# TMS570LS0914_all.net
KiCad netlist of a schematic drawn in Altium Designer
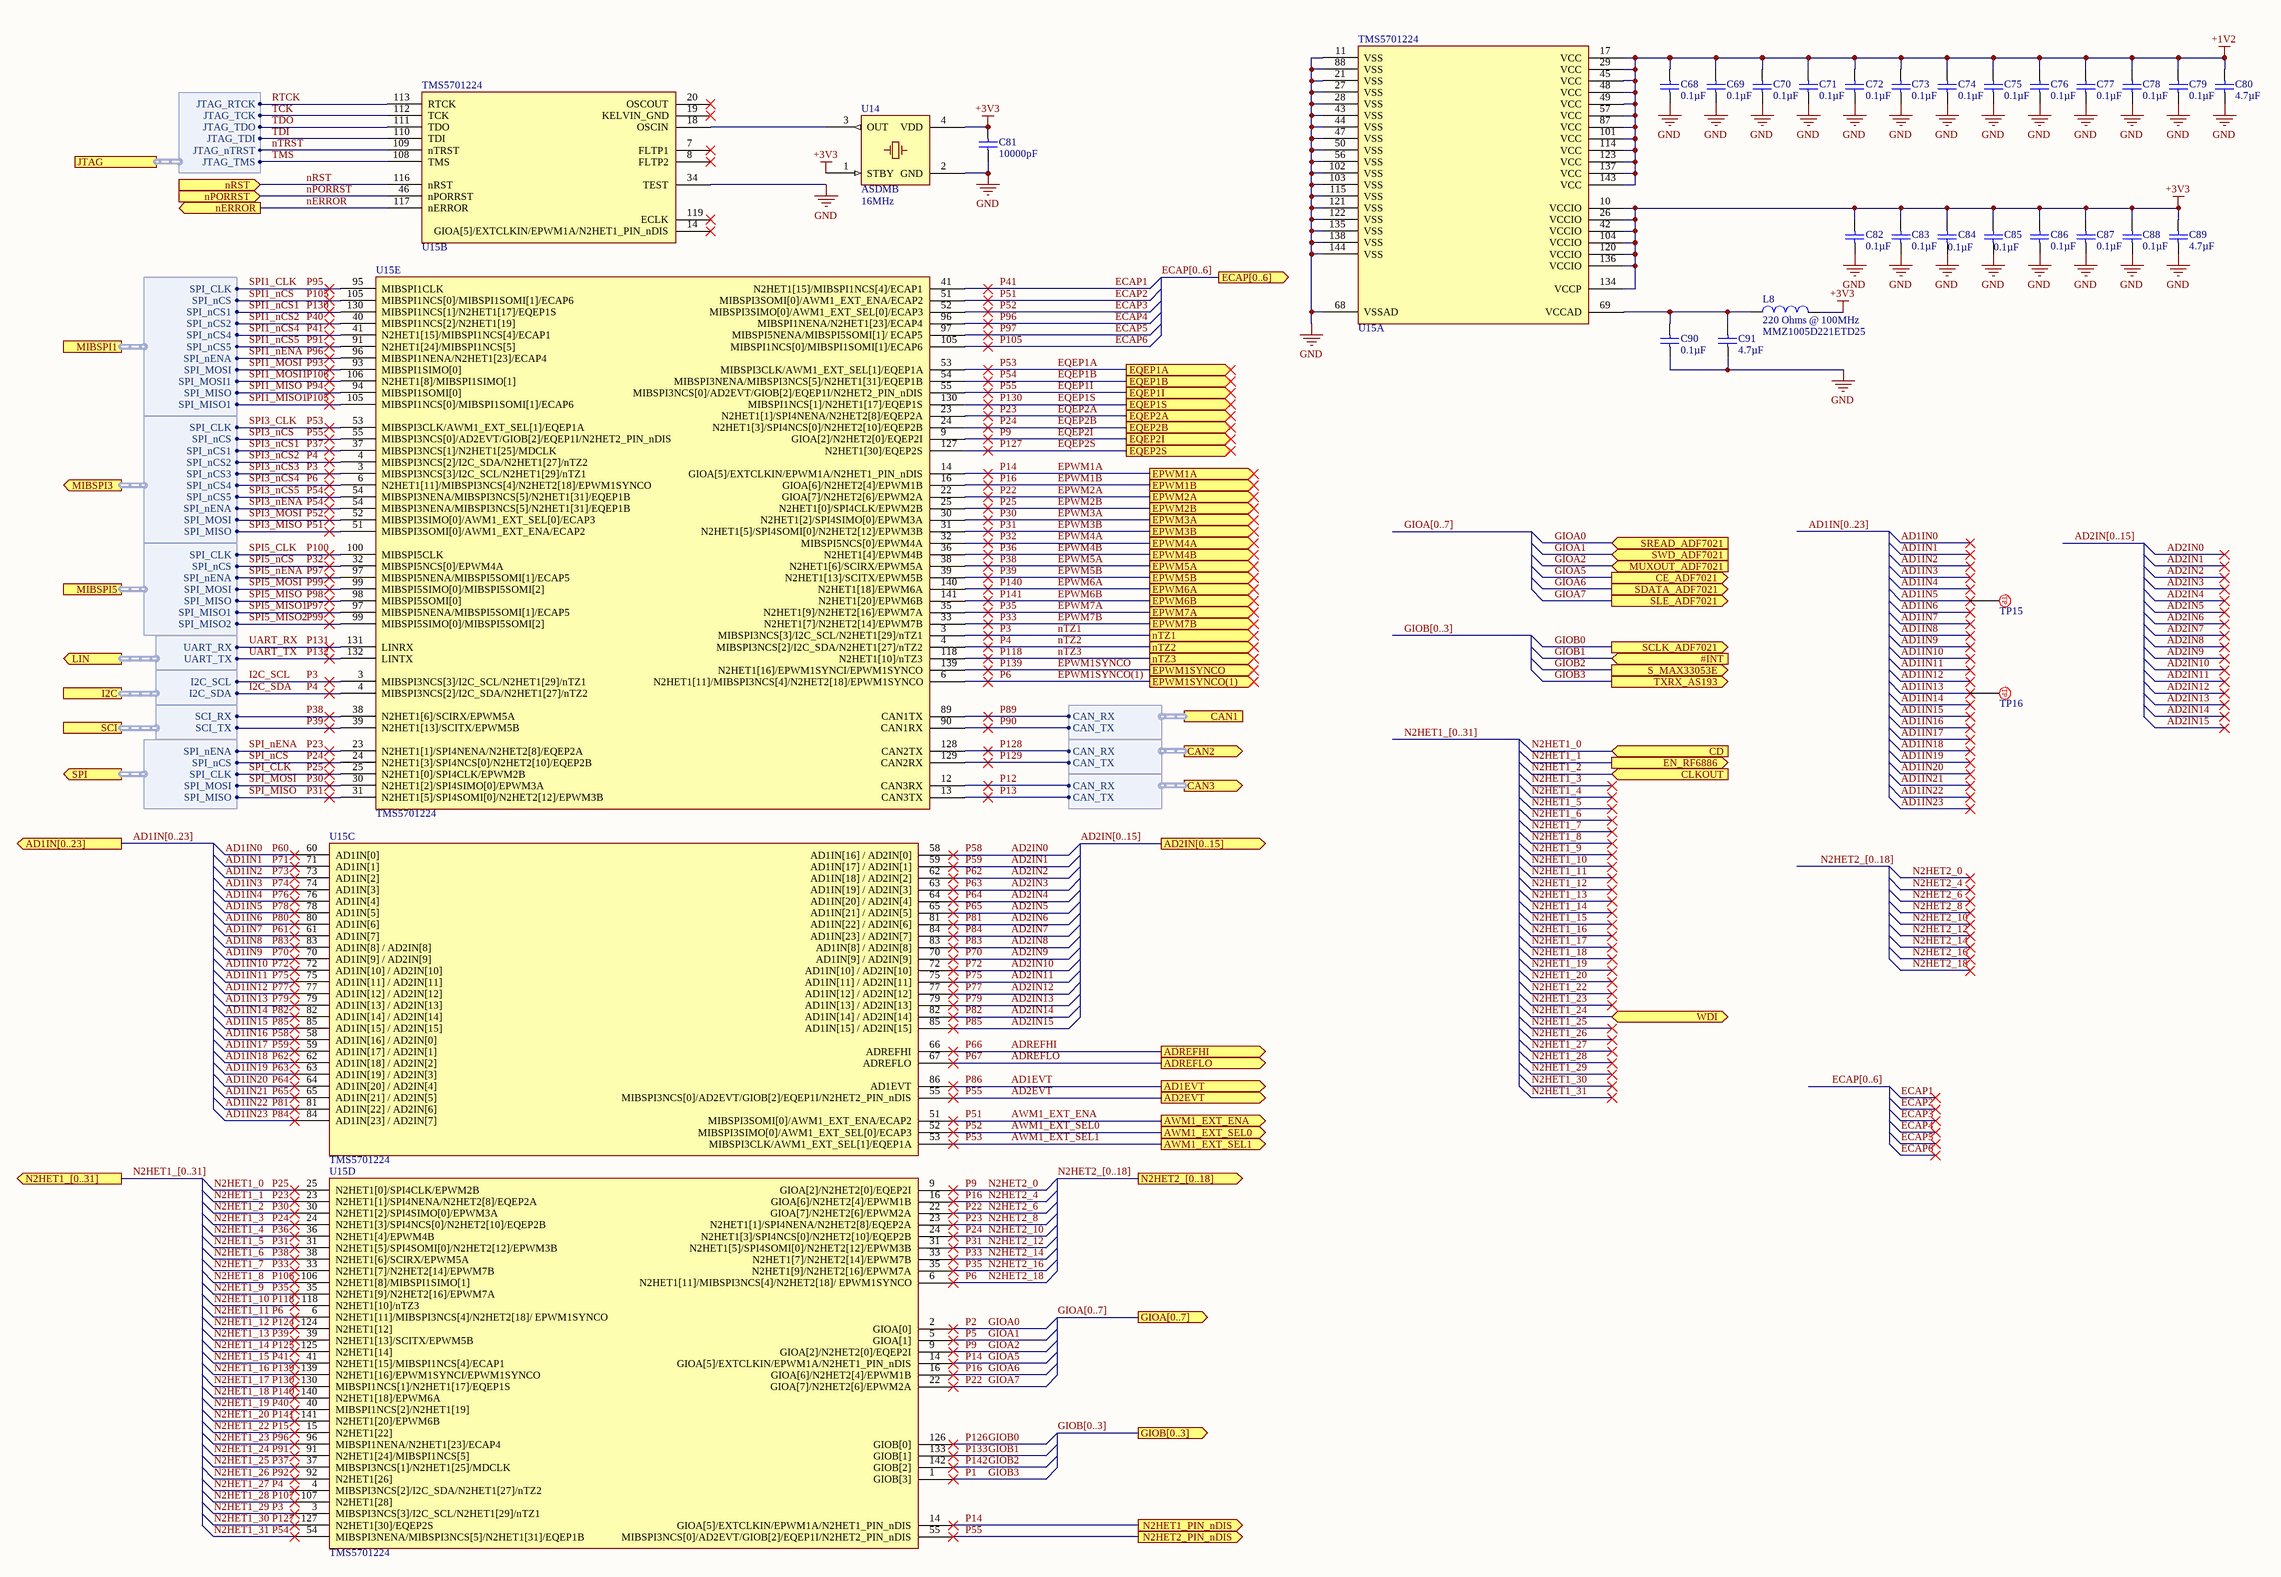
[diagram p0: TMS570LS0914_all.SchDoc]

(export (version "E")
  (design (tool "Eeschema 10.0.6"))
  (components
    (comp (ref "C68")
      (value "0.1µF")
      (footprint "TDK-CGA2B")
      (description "CAP CER 0.1UF 50V X7R 0402")
      (fields
        (field (name "PART NUMBER") "PC-TDK-02262")
        (field (name "MANUFACTURER PART NUMBER") "CGA2B3X7R1H104M050BB")
        (field (name "PUBLISHER") "AlbertaSat")
      )
      (libsource (lib "Database") (part "Cap"))
    )
    (comp (ref "C69")
      (value "0.1µF")
      (footprint "TDK-CGA2B")
      (description "CAP CER 0.1UF 50V X7R 0402")
      (fields
        (field (name "PART NUMBER") "PC-TDK-02262")
        (field (name "MANUFACTURER PART NUMBER") "CGA2B3X7R1H104M050BB")
        (field (name "PUBLISHER") "AlbertaSat")
      )
      (libsource (lib "Database") (part "Cap"))
    )
    (comp (ref "C70")
      (value "0.1µF")
      (footprint "TDK-CGA2B")
      (description "CAP CER 0.1UF 50V X7R 0402")
      (fields
        (field (name "PART NUMBER") "PC-TDK-02262")
        (field (name "MANUFACTURER PART NUMBER") "CGA2B3X7R1H104M050BB")
        (field (name "PUBLISHER") "AlbertaSat")
      )
      (libsource (lib "Database") (part "Cap"))
    )
    (comp (ref "C71")
      (value "0.1µF")
      (footprint "TDK-CGA2B")
      (description "CAP CER 0.1UF 50V X7R 0402")
      (fields
        (field (name "PART NUMBER") "PC-TDK-02262")
        (field (name "MANUFACTURER PART NUMBER") "CGA2B3X7R1H104M050BB")
        (field (name "PUBLISHER") "AlbertaSat")
      )
      (libsource (lib "Database") (part "Cap"))
    )
    (comp (ref "C72")
      (value "0.1µF")
      (footprint "TDK-CGA2B")
      (description "CAP CER 0.1UF 50V X7R 0402")
      (fields
        (field (name "PART NUMBER") "PC-TDK-02262")
        (field (name "MANUFACTURER PART NUMBER") "CGA2B3X7R1H104M050BB")
        (field (name "PUBLISHER") "AlbertaSat")
      )
      (libsource (lib "Database") (part "Cap"))
    )
    (comp (ref "C73")
      (value "0.1µF")
      (footprint "TDK-CGA2B")
      (description "CAP CER 0.1UF 50V X7R 0402")
      (fields
        (field (name "PART NUMBER") "PC-TDK-02262")
        (field (name "MANUFACTURER PART NUMBER") "CGA2B3X7R1H104M050BB")
        (field (name "PUBLISHER") "AlbertaSat")
      )
      (libsource (lib "Database") (part "Cap"))
    )
    (comp (ref "C74")
      (value "0.1µF")
      (footprint "TDK-CGA2B")
      (description "CAP CER 0.1UF 50V X7R 0402")
      (fields
        (field (name "PART NUMBER") "PC-TDK-02262")
        (field (name "MANUFACTURER PART NUMBER") "CGA2B3X7R1H104M050BB")
        (field (name "PUBLISHER") "AlbertaSat")
      )
      (libsource (lib "Database") (part "Cap"))
    )
    (comp (ref "C75")
      (value "0.1µF")
      (footprint "TDK-CGA2B")
      (description "CAP CER 0.1UF 50V X7R 0402")
      (fields
        (field (name "PART NUMBER") "PC-TDK-02262")
        (field (name "MANUFACTURER PART NUMBER") "CGA2B3X7R1H104M050BB")
        (field (name "PUBLISHER") "AlbertaSat")
      )
      (libsource (lib "Database") (part "Cap"))
    )
    (comp (ref "C76")
      (value "0.1µF")
      (footprint "TDK-CGA2B")
      (description "CAP CER 0.1UF 50V X7R 0402")
      (fields
        (field (name "PART NUMBER") "PC-TDK-02262")
        (field (name "MANUFACTURER PART NUMBER") "CGA2B3X7R1H104M050BB")
        (field (name "PUBLISHER") "AlbertaSat")
      )
      (libsource (lib "Database") (part "Cap"))
    )
    (comp (ref "C77")
      (value "0.1µF")
      (footprint "TDK-CGA2B")
      (description "CAP CER 0.1UF 50V X7R 0402")
      (fields
        (field (name "PART NUMBER") "PC-TDK-02262")
        (field (name "MANUFACTURER PART NUMBER") "CGA2B3X7R1H104M050BB")
        (field (name "PUBLISHER") "AlbertaSat")
      )
      (libsource (lib "Database") (part "Cap"))
    )
    (comp (ref "C78")
      (value "0.1µF")
      (footprint "TDK-CGA2B")
      (description "CAP CER 0.1UF 50V X7R 0402")
      (fields
        (field (name "PART NUMBER") "PC-TDK-02262")
        (field (name "MANUFACTURER PART NUMBER") "CGA2B3X7R1H104M050BB")
        (field (name "PUBLISHER") "AlbertaSat")
      )
      (libsource (lib "Database") (part "Cap"))
    )
    (comp (ref "C79")
      (value "0.1µF")
      (footprint "TDK-CGA2B")
      (description "CAP CER 0.1UF 50V X7R 0402")
      (fields
        (field (name "PART NUMBER") "PC-TDK-02262")
        (field (name "MANUFACTURER PART NUMBER") "CGA2B3X7R1H104M050BB")
        (field (name "PUBLISHER") "AlbertaSat")
      )
      (libsource (lib "Database") (part "Cap"))
    )
    (comp (ref "C80")
      (value "4.7µF")
      (footprint "TDK-CGA4J")
      (description "CAP CER 4.7UF 25V X7R 0805")
      (fields
        (field (name "PART NUMBER") "PC-TDK-02831")
        (field (name "MANUFACTURER PART NUMBER") "CGA4J1X7R1E475M125AC")
        (field (name "PUBLISHER") "AlbertaSat")
      )
      (libsource (lib "Database") (part "Cap"))
    )
    (comp (ref "C81")
      (value "10000pF")
      (footprint "TDK-CGA2B")
      (description "CAP CER 10000PF 50V X8R 0402")
      (fields
        (field (name "PART NUMBER") "PC-TDK-01877")
        (field (name "MANUFACTURER PART NUMBER") "CGA2B3X8R1H103K050BB")
        (field (name "PUBLISHER") "AlbertaSat")
      )
      (libsource (lib "Database") (part "Cap"))
    )
    (comp (ref "C82")
      (value "0.1µF")
      (footprint "TDK-CGA2B")
      (description "CAP CER 0.1UF 50V X7R 0402")
      (fields
        (field (name "PART NUMBER") "PC-TDK-02262")
        (field (name "MANUFACTURER PART NUMBER") "CGA2B3X7R1H104M050BB")
        (field (name "PUBLISHER") "AlbertaSat")
      )
      (libsource (lib "Database") (part "Cap"))
    )
    (comp (ref "C83")
      (value "0.1µF")
      (footprint "TDK-CGA2B")
      (description "CAP CER 0.1UF 50V X7R 0402")
      (fields
        (field (name "PART NUMBER") "PC-TDK-02262")
        (field (name "MANUFACTURER PART NUMBER") "CGA2B3X7R1H104M050BB")
        (field (name "PUBLISHER") "AlbertaSat")
      )
      (libsource (lib "Database") (part "Cap"))
    )
    (comp (ref "C84")
      (value "0.1µF")
      (footprint "TDK-CGA2B")
      (description "CAP CER 0.1UF 50V X7R 0402")
      (fields
        (field (name "PART NUMBER") "PC-TDK-02262")
        (field (name "MANUFACTURER PART NUMBER") "CGA2B3X7R1H104M050BB")
        (field (name "PUBLISHER") "AlbertaSat")
      )
      (libsource (lib "Database") (part "Cap"))
    )
    (comp (ref "C85")
      (value "0.1µF")
      (footprint "TDK-CGA2B")
      (description "CAP CER 0.1UF 50V X7R 0402")
      (fields
        (field (name "PART NUMBER") "PC-TDK-02262")
        (field (name "MANUFACTURER PART NUMBER") "CGA2B3X7R1H104M050BB")
        (field (name "PUBLISHER") "AlbertaSat")
      )
      (libsource (lib "Database") (part "Cap"))
    )
    (comp (ref "C86")
      (value "0.1µF")
      (footprint "TDK-CGA2B")
      (description "CAP CER 0.1UF 50V X7R 0402")
      (fields
        (field (name "PART NUMBER") "PC-TDK-02262")
        (field (name "MANUFACTURER PART NUMBER") "CGA2B3X7R1H104M050BB")
        (field (name "PUBLISHER") "AlbertaSat")
      )
      (libsource (lib "Database") (part "Cap"))
    )
    (comp (ref "C87")
      (value "0.1µF")
      (footprint "TDK-CGA2B")
      (description "CAP CER 0.1UF 50V X7R 0402")
      (fields
        (field (name "PART NUMBER") "PC-TDK-02262")
        (field (name "MANUFACTURER PART NUMBER") "CGA2B3X7R1H104M050BB")
        (field (name "PUBLISHER") "AlbertaSat")
      )
      (libsource (lib "Database") (part "Cap"))
    )
    (comp (ref "C88")
      (value "0.1µF")
      (footprint "TDK-CGA2B")
      (description "CAP CER 0.1UF 50V X7R 0402")
      (fields
        (field (name "PART NUMBER") "PC-TDK-02262")
        (field (name "MANUFACTURER PART NUMBER") "CGA2B3X7R1H104M050BB")
        (field (name "PUBLISHER") "AlbertaSat")
      )
      (libsource (lib "Database") (part "Cap"))
    )
    (comp (ref "C89")
      (value "4.7µF")
      (footprint "TDK-CGA4J")
      (description "CAP CER 4.7UF 25V X7R 0805")
      (fields
        (field (name "PART NUMBER") "PC-TDK-02831")
        (field (name "MANUFACTURER PART NUMBER") "CGA4J1X7R1E475M125AC")
        (field (name "PUBLISHER") "AlbertaSat")
      )
      (libsource (lib "Database") (part "Cap"))
    )
    (comp (ref "C90")
      (value "0.1µF")
      (footprint "TDK-CGA2B")
      (description "CAP CER 0.1UF 50V X7R 0402")
      (fields
        (field (name "PART NUMBER") "PC-TDK-02262")
        (field (name "MANUFACTURER PART NUMBER") "CGA2B3X7R1H104M050BB")
        (field (name "PUBLISHER") "AlbertaSat")
      )
      (libsource (lib "Database") (part "Cap"))
    )
    (comp (ref "C91")
      (value "4.7µF")
      (footprint "TDK-CGA4J")
      (description "CAP CER 4.7UF 25V X7R 0805")
      (fields
        (field (name "PART NUMBER") "PC-TDK-02831")
        (field (name "MANUFACTURER PART NUMBER") "CGA4J1X7R1E475M125AC")
        (field (name "PUBLISHER") "AlbertaSat")
      )
      (libsource (lib "Database") (part "Cap"))
    )
    (comp (ref "L8")
      (value "220 Ohms @ 100MHz")
      (footprint "TDK-MMZ1005")
      (description "1005")
      (fields
        (field (name "PART NUMBER") "PL-TDK-02958")
        (field (name "MANUFACTURER PART NUMBER") "MMZ1005D221ETD25")
        (field (name "Comment") "Inductor")
        (field (name "PUBLISHER") "AlbertaSat")
      )
      (libsource (lib "Database") (part "Inductor"))
    )
    (comp (ref "TP15")
      (value "5017")
      (footprint "KS-5017")
      (description "PC TEST POINT MINI SMD")
      (fields (field (name "PART NUMBER") "PTP-KS-00001") (field (name "PUBLISHER") "AlbertaSat"))
      (libsource (lib "Database") (part "5017"))
    )
    (comp (ref "TP16")
      (value "5017")
      (footprint "KS-5017")
      (description "PC TEST POINT MINI SMD")
      (fields (field (name "PART NUMBER") "PTP-KS-00001") (field (name "PUBLISHER") "AlbertaSat"))
      (libsource (lib "Database") (part "5017"))
    )
    (comp (ref "U14")
      (value "ASDMB")
      (footprint "ABR-ASDMB")
      (description "OSC MEMS 16.000MHZ CMOS SMD")
      (fields
        (field (name "PART NUMBER") "PU-ABR-00014")
        (field (name "MANUFACTURER PART NUMBER") "ASDMB-16.000MHZ-XY-T")
        (field (name "ALTIUM_VALUE") "16MHz")
        (field (name "PUBLISHER") "AlbertaSat")
      )
      (libsource (lib "Database") (part "ASDMB"))
    )
    (comp (ref "U15")
      (value "TMS5701224")
      (footprint "TI-S-PQFP-G144")
      (description "IC MCU 32BIT 1.25MB FLASH 144QFP")
      (fields (field (name "PART NUMBER") "59") (field (name "MANUFACTURER PART NUMBER") "TMS5701224CPGEQQ1"))
      (libsource (lib "Database") (part "TMS5701224CPGEQQ1"))
    )
  )
  (nets
    (net (code "26") (name "+1V2") (class "Default")
      (node (ref "C68") (pin "2") (pinfunction "2_2") (pintype "passive"))
      (node (ref "C69") (pin "2") (pinfunction "2_2") (pintype "passive"))
      (node (ref "C70") (pin "2") (pinfunction "2_2") (pintype "passive"))
      (node (ref "C71") (pin "2") (pinfunction "2_2") (pintype "passive"))
      (node (ref "C72") (pin "2") (pinfunction "2_2") (pintype "passive"))
      (node (ref "C73") (pin "2") (pinfunction "2_2") (pintype "passive"))
      (node (ref "C74") (pin "2") (pinfunction "2_2") (pintype "passive"))
      (node (ref "C75") (pin "2") (pinfunction "2_2") (pintype "passive"))
      (node (ref "C76") (pin "2") (pinfunction "2_2") (pintype "passive"))
      (node (ref "C77") (pin "2") (pinfunction "2_2") (pintype "passive"))
      (node (ref "C78") (pin "2") (pinfunction "2_2") (pintype "passive"))
      (node (ref "C79") (pin "2") (pinfunction "2_2") (pintype "passive"))
      (node (ref "C80") (pin "2") (pinfunction "2_2") (pintype "passive"))
      (node (ref "U15") (pin "101") (pinfunction "VCC_101") (pintype "passive"))
      (node (ref "U15") (pin "114") (pinfunction "VCC_114") (pintype "passive"))
      (node (ref "U15") (pin "123") (pinfunction "VCC_123") (pintype "passive"))
      (node (ref "U15") (pin "137") (pinfunction "VCC_137") (pintype "passive"))
      (node (ref "U15") (pin "143") (pinfunction "VCC_143") (pintype "passive"))
      (node (ref "U15") (pin "17") (pinfunction "VCC_17") (pintype "passive"))
      (node (ref "U15") (pin "29") (pinfunction "VCC_29") (pintype "passive"))
      (node (ref "U15") (pin "45") (pinfunction "VCC_45") (pintype "passive"))
      (node (ref "U15") (pin "48") (pinfunction "VCC_48") (pintype "passive"))
      (node (ref "U15") (pin "49") (pinfunction "VCC_49") (pintype "passive"))
      (node (ref "U15") (pin "57") (pinfunction "VCC_57") (pintype "passive"))
      (node (ref "U15") (pin "87") (pinfunction "VCC_87") (pintype "passive"))
    )
    (net (code "27") (name "+3V3") (class "Default")
      (node (ref "C81") (pin "2") (pinfunction "2_2") (pintype "passive"))
      (node (ref "C82") (pin "2") (pinfunction "2_2") (pintype "passive"))
      (node (ref "C83") (pin "2") (pinfunction "2_2") (pintype "passive"))
      (node (ref "C84") (pin "2") (pinfunction "2_2") (pintype "passive"))
      (node (ref "C85") (pin "2") (pinfunction "2_2") (pintype "passive"))
      (node (ref "C86") (pin "2") (pinfunction "2_2") (pintype "passive"))
      (node (ref "C87") (pin "2") (pinfunction "2_2") (pintype "passive"))
      (node (ref "C88") (pin "2") (pinfunction "2_2") (pintype "passive"))
      (node (ref "C89") (pin "2") (pinfunction "2_2") (pintype "passive"))
      (node (ref "L8") (pin "1") (pinfunction "1_1") (pintype "passive"))
      (node (ref "U14") (pin "1") (pinfunction "STBY_1") (pintype "input"))
      (node (ref "U14") (pin "4") (pinfunction "VDD_4") (pintype "power_in"))
      (node (ref "U15") (pin "10") (pinfunction "VCCIO_10") (pintype "passive"))
      (node (ref "U15") (pin "104") (pinfunction "VCCIO_104") (pintype "passive"))
      (node (ref "U15") (pin "120") (pinfunction "VCCIO_120") (pintype "passive"))
      (node (ref "U15") (pin "134") (pinfunction "VCCP_134") (pintype "passive"))
      (node (ref "U15") (pin "136") (pinfunction "VCCIO_136") (pintype "passive"))
      (node (ref "U15") (pin "26") (pinfunction "VCCIO_26") (pintype "passive"))
      (node (ref "U15") (pin "42") (pinfunction "VCCIO_42") (pintype "passive"))
    )
    (net (code "28") (name "/AD1EVT") (class "Default")
      (node (ref "U15") (pin "86") (pinfunction "AD1EVT_86") (pintype "passive+no_connect"))
    )
    (net (code "29") (name "/AD1IN0") (class "Default")
      (node (ref "U15") (pin "60") (pinfunction "AD1IN[0]_60") (pintype "passive+no_connect"))
    )
    (net (code "30") (name "/AD1IN1") (class "Default")
      (node (ref "U15") (pin "71") (pinfunction "AD1IN[1]_71") (pintype "passive+no_connect"))
    )
    (net (code "31") (name "/AD1IN2") (class "Default")
      (node (ref "U15") (pin "73") (pinfunction "AD1IN[2]_73") (pintype "passive+no_connect"))
    )
    (net (code "32") (name "/AD1IN3") (class "Default")
      (node (ref "U15") (pin "74") (pinfunction "AD1IN[3]_74") (pintype "passive+no_connect"))
    )
    (net (code "33") (name "/AD1IN4") (class "Default")
      (node (ref "U15") (pin "76") (pinfunction "AD1IN[4]_76") (pintype "passive+no_connect"))
    )
    (net (code "34") (name "/AD1IN5") (class "Default")
      (node (ref "TP15") (pin "1") (pinfunction "1_1") (pintype "passive"))
      (node (ref "U15") (pin "78") (pinfunction "AD1IN[5]_78") (pintype "passive"))
    )
    (net (code "35") (name "/AD1IN6") (class "Default")
      (node (ref "U15") (pin "80") (pinfunction "AD1IN[6]_80") (pintype "passive+no_connect"))
    )
    (net (code "36") (name "/AD1IN7") (class "Default")
      (node (ref "U15") (pin "61") (pinfunction "AD1IN[7]_61") (pintype "passive+no_connect"))
    )
    (net (code "38") (name "/AD2EVT") (class "Default")
      (node (ref "U15") (pin "55") (pinfunction "MIBSPI3NCS[0]/AD2EVT/GIOB[2]/EQEP1I/N2HET2_PIN_nDIS_55") (pintype "passive+no_connect"))
    )
    (net (code "39") (name "/AD2IN0") (class "Default")
      (node (ref "U15") (pin "58") (pinfunction "AD1IN[16]_/_AD2IN[0]_58") (pintype "passive+no_connect"))
    )
    (net (code "40") (name "/AD2IN1") (class "Default")
      (node (ref "U15") (pin "59") (pinfunction "AD1IN[17]_/_AD2IN[1]_59") (pintype "passive+no_connect"))
    )
    (net (code "41") (name "/AD2IN2") (class "Default")
      (node (ref "U15") (pin "62") (pinfunction "AD1IN[18]_/_AD2IN[2]_62") (pintype "passive+no_connect"))
    )
    (net (code "42") (name "/AD2IN3") (class "Default")
      (node (ref "U15") (pin "63") (pinfunction "AD1IN[19]_/_AD2IN[3]_63") (pintype "passive+no_connect"))
    )
    (net (code "43") (name "/AD2IN4") (class "Default")
      (node (ref "U15") (pin "64") (pinfunction "AD1IN[20]_/_AD2IN[4]_64") (pintype "passive+no_connect"))
    )
    (net (code "44") (name "/AD2IN5") (class "Default")
      (node (ref "U15") (pin "65") (pinfunction "AD1IN[21]_/_AD2IN[5]_65") (pintype "passive+no_connect"))
    )
    (net (code "45") (name "/AD2IN6") (class "Default")
      (node (ref "U15") (pin "81") (pinfunction "AD1IN[22]_/_AD2IN[6]_81") (pintype "passive+no_connect"))
    )
    (net (code "46") (name "/AD2IN7") (class "Default")
      (node (ref "U15") (pin "84") (pinfunction "AD1IN[23]_/_AD2IN[7]_84") (pintype "passive+no_connect"))
    )
    (net (code "47") (name "/AD2IN8") (class "Default")
      (node (ref "U15") (pin "83") (pinfunction "AD1IN[8]_/_AD2IN[8]_83") (pintype "passive+no_connect"))
    )
    (net (code "48") (name "/AD2IN9") (class "Default")
      (node (ref "U15") (pin "70") (pinfunction "AD1IN[9]_/_AD2IN[9]_70") (pintype "passive+no_connect"))
    )
    (net (code "49") (name "/AD2IN10") (class "Default")
      (node (ref "U15") (pin "72") (pinfunction "AD1IN[10]_/_AD2IN[10]_72") (pintype "passive+no_connect"))
    )
    (net (code "50") (name "/AD2IN11") (class "Default")
      (node (ref "U15") (pin "75") (pinfunction "AD1IN[11]_/_AD2IN[11]_75") (pintype "passive+no_connect"))
    )
    (net (code "51") (name "/AD2IN12") (class "Default")
      (node (ref "U15") (pin "77") (pinfunction "AD1IN[12]_/_AD2IN[12]_77") (pintype "passive+no_connect"))
    )
    (net (code "52") (name "/AD2IN13") (class "Default")
      (node (ref "TP16") (pin "1") (pinfunction "1_1") (pintype "passive"))
      (node (ref "U15") (pin "79") (pinfunction "AD1IN[13]_/_AD2IN[13]_79") (pintype "passive"))
    )
    (net (code "53") (name "/AD2IN14") (class "Default")
      (node (ref "U15") (pin "82") (pinfunction "AD1IN[14]_/_AD2IN[14]_82") (pintype "passive+no_connect"))
    )
    (net (code "54") (name "/AD2IN15") (class "Default")
      (node (ref "U15") (pin "85") (pinfunction "AD1IN[15]_/_AD2IN[15]_85") (pintype "passive+no_connect"))
    )
    (net (code "56") (name "/ADREFHI") (class "Default")
      (node (ref "U15") (pin "66") (pinfunction "ADREFHI_66") (pintype "passive+no_connect"))
    )
    (net (code "57") (name "/ADREFLO") (class "Default")
      (node (ref "U15") (pin "67") (pinfunction "ADREFLO_67") (pintype "passive+no_connect"))
    )
    (net (code "58") (name "/AWM1_EXT_SEL1") (class "Default")
      (node (ref "U15") (pin "53") (pinfunction "MIBSPI3CLK/AWM1_EXT_SEL[1]/EQEP1A_53") (pintype "passive+no_connect"))
    )
    (net (code "59") (name "/ECAP2") (class "Default")
      (node (ref "U15") (pin "51") (pinfunction "MIBSPI3SOMI[0]/AWM1_EXT_ENA/ECAP2_51") (pintype "passive+no_connect"))
    )
    (net (code "60") (name "/ECAP3") (class "Default")
      (node (ref "U15") (pin "52") (pinfunction "MIBSPI3SIMO[0]/AWM1_EXT_SEL[0]/ECAP3_52") (pintype "passive+no_connect"))
    )
    (net (code "61") (name "/ECAP5") (class "Default")
      (node (ref "U15") (pin "97") (pinfunction "MIBSPI5NENA/MIBSPI5SOMI[1]/ECAP5_97") (pintype "passive+no_connect"))
    )
    (net (code "62") (name "/ECAP6") (class "Default")
      (node (ref "U15") (pin "105") (pinfunction "MIBSPI1NCS[0]/MIBSPI1SOMI[1]/ECAP6_105") (pintype "passive+no_connect"))
    )
    (net (code "64") (name "/EPWM4A") (class "Default")
      (node (ref "U15") (pin "32") (pinfunction "MIBSPI5NCS[0]/EPWM4A_32") (pintype "passive"))
    )
    (net (code "65") (name "/GIOA0") (class "Default")
      (node (ref "U15") (pin "2") (pinfunction "GIOA[0]_2") (pintype "passive+no_connect"))
    )
    (net (code "66") (name "/GIOA1") (class "Default")
      (node (ref "U15") (pin "5") (pinfunction "GIOA[1]_5") (pintype "passive+no_connect"))
    )
    (net (code "67") (name "/GIOA2") (class "Default")
      (node (ref "U15") (pin "9") (pinfunction "GIOA[2]/N2HET2[0]/EQEP2I_9") (pintype "passive+no_connect"))
    )
    (net (code "68") (name "/GIOA5") (class "Default")
      (node (ref "U15") (pin "14") (pinfunction "GIOA[5]/EXTCLKIN/EPWM1A/N2HET1_PIN_nDIS_14") (pintype "passive+no_connect"))
    )
    (net (code "69") (name "/GIOA6") (class "Default")
      (node (ref "U15") (pin "16") (pinfunction "GIOA[6]/N2HET2[4]/EPWM1B_16") (pintype "passive"))
    )
    (net (code "70") (name "/GIOA7") (class "Default")
      (node (ref "U15") (pin "22") (pinfunction "GIOA[7]/N2HET2[6]/EPWM2A_22") (pintype "passive"))
    )
    (net (code "72") (name "/GIOB0") (class "Default")
      (node (ref "U15") (pin "126") (pinfunction "GIOB[0]_126") (pintype "passive+no_connect"))
    )
    (net (code "73") (name "/GIOB1") (class "Default")
      (node (ref "U15") (pin "133") (pinfunction "GIOB[1]_133") (pintype "passive+no_connect"))
    )
    (net (code "74") (name "/GIOB2") (class "Default")
      (node (ref "U15") (pin "142") (pinfunction "GIOB[2]_142") (pintype "passive+no_connect"))
    )
    (net (code "75") (name "/GIOB3") (class "Default")
      (node (ref "U15") (pin "1") (pinfunction "GIOB[3]_1") (pintype "passive+no_connect"))
    )
    (net (code "77") (name "/N2HET1_0") (class "Default")
      (node (ref "U15") (pin "25") (pinfunction "N2HET1[0]/SPI4CLK/EPWM2B_25") (pintype "passive"))
    )
    (net (code "78") (name "/N2HET1_1") (class "Default")
      (node (ref "U15") (pin "23") (pinfunction "N2HET1[1]/SPI4NENA/N2HET2[8]/EQEP2A_23") (pintype "passive"))
    )
    (net (code "79") (name "/N2HET1_2") (class "Default")
      (node (ref "U15") (pin "30") (pinfunction "N2HET1[2]/SPI4SIMO[0]/EPWM3A_30") (pintype "passive"))
    )
    (net (code "80") (name "/N2HET1_3") (class "Default")
      (node (ref "U15") (pin "24") (pinfunction "N2HET1[3]/SPI4NCS[0]/N2HET2[10]/EQEP2B_24") (pintype "passive+no_connect"))
    )
    (net (code "81") (name "/N2HET1_4") (class "Default")
      (node (ref "U15") (pin "36") (pinfunction "N2HET1[4]/EPWM4B_36") (pintype "passive+no_connect"))
    )
    (net (code "82") (name "/N2HET1_5") (class "Default")
      (node (ref "U15") (pin "31") (pinfunction "N2HET1[5]/SPI4SOMI[0]/N2HET2[12]/EPWM3B_31") (pintype "passive+no_connect"))
    )
    (net (code "83") (name "/N2HET1_6") (class "Default")
      (node (ref "U15") (pin "38") (pinfunction "N2HET1[6]/SCIRX/EPWM5A_38") (pintype "passive+no_connect"))
    )
    (net (code "84") (name "/N2HET1_7") (class "Default")
      (node (ref "U15") (pin "33") (pinfunction "N2HET1[7]/N2HET2[14]/EPWM7B_33") (pintype "passive+no_connect"))
    )
    (net (code "85") (name "/N2HET1_8") (class "Default")
      (node (ref "U15") (pin "106") (pinfunction "N2HET1[8]/MIBSPI1SIMO[1]_106") (pintype "passive+no_connect"))
    )
    (net (code "86") (name "/N2HET1_9") (class "Default")
      (node (ref "U15") (pin "35") (pinfunction "N2HET1[9]/N2HET2[16]/EPWM7A_35") (pintype "passive+no_connect"))
    )
    (net (code "87") (name "/N2HET1_10") (class "Default")
      (node (ref "U15") (pin "118") (pinfunction "N2HET1[10]/nTZ3_118") (pintype "passive+no_connect"))
    )
    (net (code "88") (name "/N2HET1_11") (class "Default")
      (node (ref "U15") (pin "6") (pinfunction "N2HET1[11]/MIBSPI3NCS[4]/N2HET2[18]/_EPWM1SYNCO_6") (pintype "passive+no_connect"))
    )
    (net (code "89") (name "/N2HET1_12") (class "Default")
      (node (ref "U15") (pin "124") (pinfunction "N2HET1[12]_124") (pintype "passive+no_connect"))
    )
    (net (code "90") (name "/N2HET1_13") (class "Default")
      (node (ref "U15") (pin "39") (pinfunction "N2HET1[13]/SCITX/EPWM5B_39") (pintype "passive+no_connect"))
    )
    (net (code "91") (name "/N2HET1_14") (class "Default")
      (node (ref "U15") (pin "125") (pinfunction "N2HET1[14]_125") (pintype "passive+no_connect"))
    )
    (net (code "92") (name "/N2HET1_15") (class "Default")
      (node (ref "U15") (pin "41") (pinfunction "N2HET1[15]/MIBSPI1NCS[4]/ECAP1_41") (pintype "passive+no_connect"))
    )
    (net (code "93") (name "/N2HET1_16") (class "Default")
      (node (ref "U15") (pin "139") (pinfunction "N2HET1[16]/EPWM1SYNCI/EPWM1SYNCO_139") (pintype "passive+no_connect"))
    )
    (net (code "94") (name "/N2HET1_17") (class "Default")
      (node (ref "U15") (pin "130") (pinfunction "MIBSPI1NCS[1]/N2HET1[17]/EQEP1S_130") (pintype "passive+no_connect"))
    )
    (net (code "95") (name "/N2HET1_18") (class "Default")
      (node (ref "U15") (pin "140") (pinfunction "N2HET1[18]/EPWM6A_140") (pintype "passive+no_connect"))
    )
    (net (code "96") (name "/N2HET1_19") (class "Default")
      (node (ref "U15") (pin "40") (pinfunction "MIBSPI1NCS[2]/N2HET1[19]_40") (pintype "passive+no_connect"))
    )
    (net (code "97") (name "/N2HET1_20") (class "Default")
      (node (ref "U15") (pin "141") (pinfunction "N2HET1[20]/EPWM6B_141") (pintype "passive+no_connect"))
    )
    (net (code "98") (name "/N2HET1_22") (class "Default")
      (node (ref "U15") (pin "15") (pinfunction "N2HET1[22]_15") (pintype "passive+no_connect"))
    )
    (net (code "99") (name "/N2HET1_23") (class "Default")
      (node (ref "U15") (pin "96") (pinfunction "MIBSPI1NENA/N2HET1[23]/ECAP4_96") (pintype "passive+no_connect"))
    )
    (net (code "100") (name "/N2HET1_24") (class "Default")
      (node (ref "U15") (pin "91") (pinfunction "N2HET1[24]/MIBSPI1NCS[5]_91") (pintype "passive"))
    )
    (net (code "101") (name "/N2HET1_25") (class "Default")
      (node (ref "U15") (pin "37") (pinfunction "MIBSPI3NCS[1]/N2HET1[25]/MDCLK_37") (pintype "passive+no_connect"))
    )
    (net (code "102") (name "/N2HET1_26") (class "Default")
      (node (ref "U15") (pin "92") (pinfunction "N2HET1[26]_92") (pintype "passive+no_connect"))
    )
    (net (code "103") (name "/N2HET1_27") (class "Default")
      (node (ref "U15") (pin "4") (pinfunction "MIBSPI3NCS[2]/I2C_SDA/N2HET1[27]/nTZ2_4") (pintype "passive+no_connect"))
    )
    (net (code "104") (name "/N2HET1_28") (class "Default")
      (node (ref "U15") (pin "107") (pinfunction "N2HET1[28]_107") (pintype "passive+no_connect"))
    )
    (net (code "105") (name "/N2HET1_29") (class "Default")
      (node (ref "U15") (pin "3") (pinfunction "MIBSPI3NCS[3]/I2C_SCL/N2HET1[29]/nTZ1_3") (pintype "passive+no_connect"))
    )
    (net (code "106") (name "/N2HET1_30") (class "Default")
      (node (ref "U15") (pin "127") (pinfunction "N2HET1[30]/EQEP2S_127") (pintype "passive+no_connect"))
    )
    (net (code "107") (name "/N2HET1_31") (class "Default")
      (node (ref "U15") (pin "54") (pinfunction "MIBSPI3NENA/MIBSPI3NCS[5]/N2HET1[31]/EQEP1B_54") (pintype "passive+no_connect"))
    )
    (net (code "110") (name "/P12") (class "Default")
      (node (ref "U15") (pin "12") (pinfunction "CAN3RX_12") (pintype "passive"))
    )
    (net (code "111") (name "/P13") (class "Default")
      (node (ref "U15") (pin "13") (pinfunction "CAN3TX_13") (pintype "passive"))
    )
    (net (code "112") (name "/P89") (class "Default")
      (node (ref "U15") (pin "89") (pinfunction "CAN1TX_89") (pintype "passive"))
    )
    (net (code "113") (name "/P90") (class "Default")
      (node (ref "U15") (pin "90") (pinfunction "CAN1RX_90") (pintype "passive"))
    )
    (net (code "114") (name "/P93") (class "Default")
      (node (ref "U15") (pin "93") (pinfunction "MIBSPI1SIMO[0]_93") (pintype "passive"))
    )
    (net (code "115") (name "/P94") (class "Default")
      (node (ref "U15") (pin "94") (pinfunction "MIBSPI1SOMI[0]_94") (pintype "passive"))
    )
    (net (code "116") (name "/P95") (class "Default")
      (node (ref "U15") (pin "95") (pinfunction "MIBSPI1CLK_95") (pintype "passive"))
    )
    (net (code "117") (name "/P98") (class "Default")
      (node (ref "U15") (pin "98") (pinfunction "MIBSPI5SOMI[0]_98") (pintype "passive"))
    )
    (net (code "118") (name "/P99") (class "Default")
      (node (ref "U15") (pin "99") (pinfunction "MIBSPI5SIMO[0]/MIBSPI5SOMI[2]_99") (pintype "passive"))
    )
    (net (code "119") (name "/P100") (class "Default")
      (node (ref "U15") (pin "100") (pinfunction "MIBSPI5CLK_100") (pintype "passive"))
    )
    (net (code "120") (name "/P128") (class "Default")
      (node (ref "U15") (pin "128") (pinfunction "CAN2TX_128") (pintype "passive"))
    )
    (net (code "121") (name "/P129") (class "Default")
      (node (ref "U15") (pin "129") (pinfunction "CAN2RX_129") (pintype "passive"))
    )
    (net (code "122") (name "/P131") (class "Default")
      (node (ref "U15") (pin "131") (pinfunction "LINRX_131") (pintype "passive"))
    )
    (net (code "123") (name "/P132") (class "Default")
      (node (ref "U15") (pin "132") (pinfunction "LINTX_132") (pintype "passive"))
    )
    (net (code "124") (name "/RTCK") (class "Default")
      (node (ref "U15") (pin "113") (pinfunction "RTCK_113") (pintype "passive"))
    )
    (net (code "125") (name "/TCK") (class "Default")
      (node (ref "U15") (pin "112") (pinfunction "TCK_112") (pintype "passive"))
    )
    (net (code "126") (name "/TDI") (class "Default")
      (node (ref "U15") (pin "110") (pinfunction "TDI_110") (pintype "passive"))
    )
    (net (code "127") (name "/TDO") (class "Default")
      (node (ref "U15") (pin "111") (pinfunction "TDO_111") (pintype "passive"))
    )
    (net (code "128") (name "/TMS") (class "Default")
      (node (ref "U15") (pin "108") (pinfunction "TMS_108") (pintype "passive"))
    )
    (net (code "129") (name "/nERROR") (class "Default")
      (node (ref "U15") (pin "117") (pinfunction "nERROR_117") (pintype "passive"))
    )
    (net (code "130") (name "/nPORRST") (class "Default")
      (node (ref "U15") (pin "46") (pinfunction "nPORRST_46") (pintype "passive"))
    )
    (net (code "131") (name "/nRST") (class "Default")
      (node (ref "U15") (pin "116") (pinfunction "nRST_116") (pintype "passive"))
    )
    (net (code "132") (name "/nTRST") (class "Default")
      (node (ref "U15") (pin "109") (pinfunction "nTRST_109") (pintype "passive"))
    )
    (net (code "144") (name "GND") (class "Default")
      (node (ref "C68") (pin "1") (pinfunction "1_1") (pintype "passive"))
      (node (ref "C69") (pin "1") (pinfunction "1_1") (pintype "passive"))
      (node (ref "C70") (pin "1") (pinfunction "1_1") (pintype "passive"))
      (node (ref "C71") (pin "1") (pinfunction "1_1") (pintype "passive"))
      (node (ref "C72") (pin "1") (pinfunction "1_1") (pintype "passive"))
      (node (ref "C73") (pin "1") (pinfunction "1_1") (pintype "passive"))
      (node (ref "C74") (pin "1") (pinfunction "1_1") (pintype "passive"))
      (node (ref "C75") (pin "1") (pinfunction "1_1") (pintype "passive"))
      (node (ref "C76") (pin "1") (pinfunction "1_1") (pintype "passive"))
      (node (ref "C77") (pin "1") (pinfunction "1_1") (pintype "passive"))
      (node (ref "C78") (pin "1") (pinfunction "1_1") (pintype "passive"))
      (node (ref "C79") (pin "1") (pinfunction "1_1") (pintype "passive"))
      (node (ref "C80") (pin "1") (pinfunction "1_1") (pintype "passive"))
      (node (ref "C81") (pin "1") (pinfunction "1_1") (pintype "passive"))
      (node (ref "C82") (pin "1") (pinfunction "1_1") (pintype "passive"))
      (node (ref "C83") (pin "1") (pinfunction "1_1") (pintype "passive"))
      (node (ref "C84") (pin "1") (pinfunction "1_1") (pintype "passive"))
      (node (ref "C85") (pin "1") (pinfunction "1_1") (pintype "passive"))
      (node (ref "C86") (pin "1") (pinfunction "1_1") (pintype "passive"))
      (node (ref "C87") (pin "1") (pinfunction "1_1") (pintype "passive"))
      (node (ref "C88") (pin "1") (pinfunction "1_1") (pintype "passive"))
      (node (ref "C89") (pin "1") (pinfunction "1_1") (pintype "passive"))
      (node (ref "C90") (pin "1") (pinfunction "1_1") (pintype "passive"))
      (node (ref "C91") (pin "1") (pinfunction "1_1") (pintype "passive"))
      (node (ref "U14") (pin "2") (pinfunction "GND_2") (pintype "power_in"))
      (node (ref "U15") (pin "102") (pinfunction "VSS_102") (pintype "passive"))
      (node (ref "U15") (pin "103") (pinfunction "VSS_103") (pintype "passive"))
      (node (ref "U15") (pin "11") (pinfunction "VSS_11") (pintype "passive"))
      (node (ref "U15") (pin "115") (pinfunction "VSS_115") (pintype "passive"))
      (node (ref "U15") (pin "121") (pinfunction "VSS_121") (pintype "passive"))
      (node (ref "U15") (pin "122") (pinfunction "VSS_122") (pintype "passive"))
      (node (ref "U15") (pin "135") (pinfunction "VSS_135") (pintype "passive"))
      (node (ref "U15") (pin "138") (pinfunction "VSS_138") (pintype "passive"))
      (node (ref "U15") (pin "144") (pinfunction "VSS_144") (pintype "passive"))
      (node (ref "U15") (pin "21") (pinfunction "VSS_21") (pintype "passive"))
      (node (ref "U15") (pin "27") (pinfunction "VSS_27") (pintype "passive"))
      (node (ref "U15") (pin "28") (pinfunction "VSS_28") (pintype "passive"))
      (node (ref "U15") (pin "34") (pinfunction "TEST_34") (pintype "passive"))
      (node (ref "U15") (pin "43") (pinfunction "VSS_43") (pintype "passive"))
      (node (ref "U15") (pin "44") (pinfunction "VSS_44") (pintype "passive"))
      (node (ref "U15") (pin "47") (pinfunction "VSS_47") (pintype "passive"))
      (node (ref "U15") (pin "50") (pinfunction "VSS_50") (pintype "passive"))
      (node (ref "U15") (pin "56") (pinfunction "VSS_56") (pintype "passive"))
      (node (ref "U15") (pin "68") (pinfunction "VSSAD_68") (pintype "passive"))
      (node (ref "U15") (pin "88") (pinfunction "VSS_88") (pintype "passive"))
    )
    (net (code "145") (name "Net-(U14-OUT)") (class "Default")
      (node (ref "U14") (pin "3") (pinfunction "OUT_3") (pintype "output"))
      (node (ref "U15") (pin "18") (pinfunction "OSCIN_18") (pintype "passive"))
    )
    (net (code "146") (name "Net-(U15A-VCCAD)") (class "Default")
      (node (ref "C90") (pin "2") (pinfunction "2_2") (pintype "passive"))
      (node (ref "C91") (pin "2") (pinfunction "2_2") (pintype "passive"))
      (node (ref "L8") (pin "2") (pinfunction "2_2") (pintype "passive"))
      (node (ref "U15") (pin "69") (pinfunction "VCCAD_69") (pintype "passive"))
    )
    (net (code "147") (name "unconnected-(U15B-ECLK-Pad119)") (class "Default")
      (node (ref "U15") (pin "119") (pinfunction "ECLK_119") (pintype "passive+no_connect"))
    )
    (net (code "148") (name "unconnected-(U15B-FLTP1-Pad7)") (class "Default")
      (node (ref "U15") (pin "7") (pinfunction "FLTP1_7") (pintype "passive+no_connect"))
    )
    (net (code "149") (name "unconnected-(U15B-FLTP2-Pad8)") (class "Default")
      (node (ref "U15") (pin "8") (pinfunction "FLTP2_8") (pintype "passive+no_connect"))
    )
    (net (code "150") (name "unconnected-(U15B-GIOA[5]{slash}EXTCLKIN{slash}EPWM1A{slash}N2HET1_PIN_nDIS-Pad14)") (class "Default")
      (node (ref "U15") (pin "14") (pinfunction "GIOA[5]/EXTCLKIN/EPWM1A/N2HET1_PIN_nDIS_14") (pintype "passive+no_connect"))
    )
    (net (code "151") (name "unconnected-(U15B-KELVIN_GND-Pad19)") (class "Default")
      (node (ref "U15") (pin "19") (pinfunction "KELVIN_GND_19") (pintype "passive+no_connect"))
    )
    (net (code "152") (name "unconnected-(U15B-OSCOUT-Pad20)") (class "Default")
      (node (ref "U15") (pin "20") (pinfunction "OSCOUT_20") (pintype "passive+no_connect"))
    )
  )
)
